# GPS_radiologger_v12.net
KiCad netlist of a schematic drawn in EAGLE
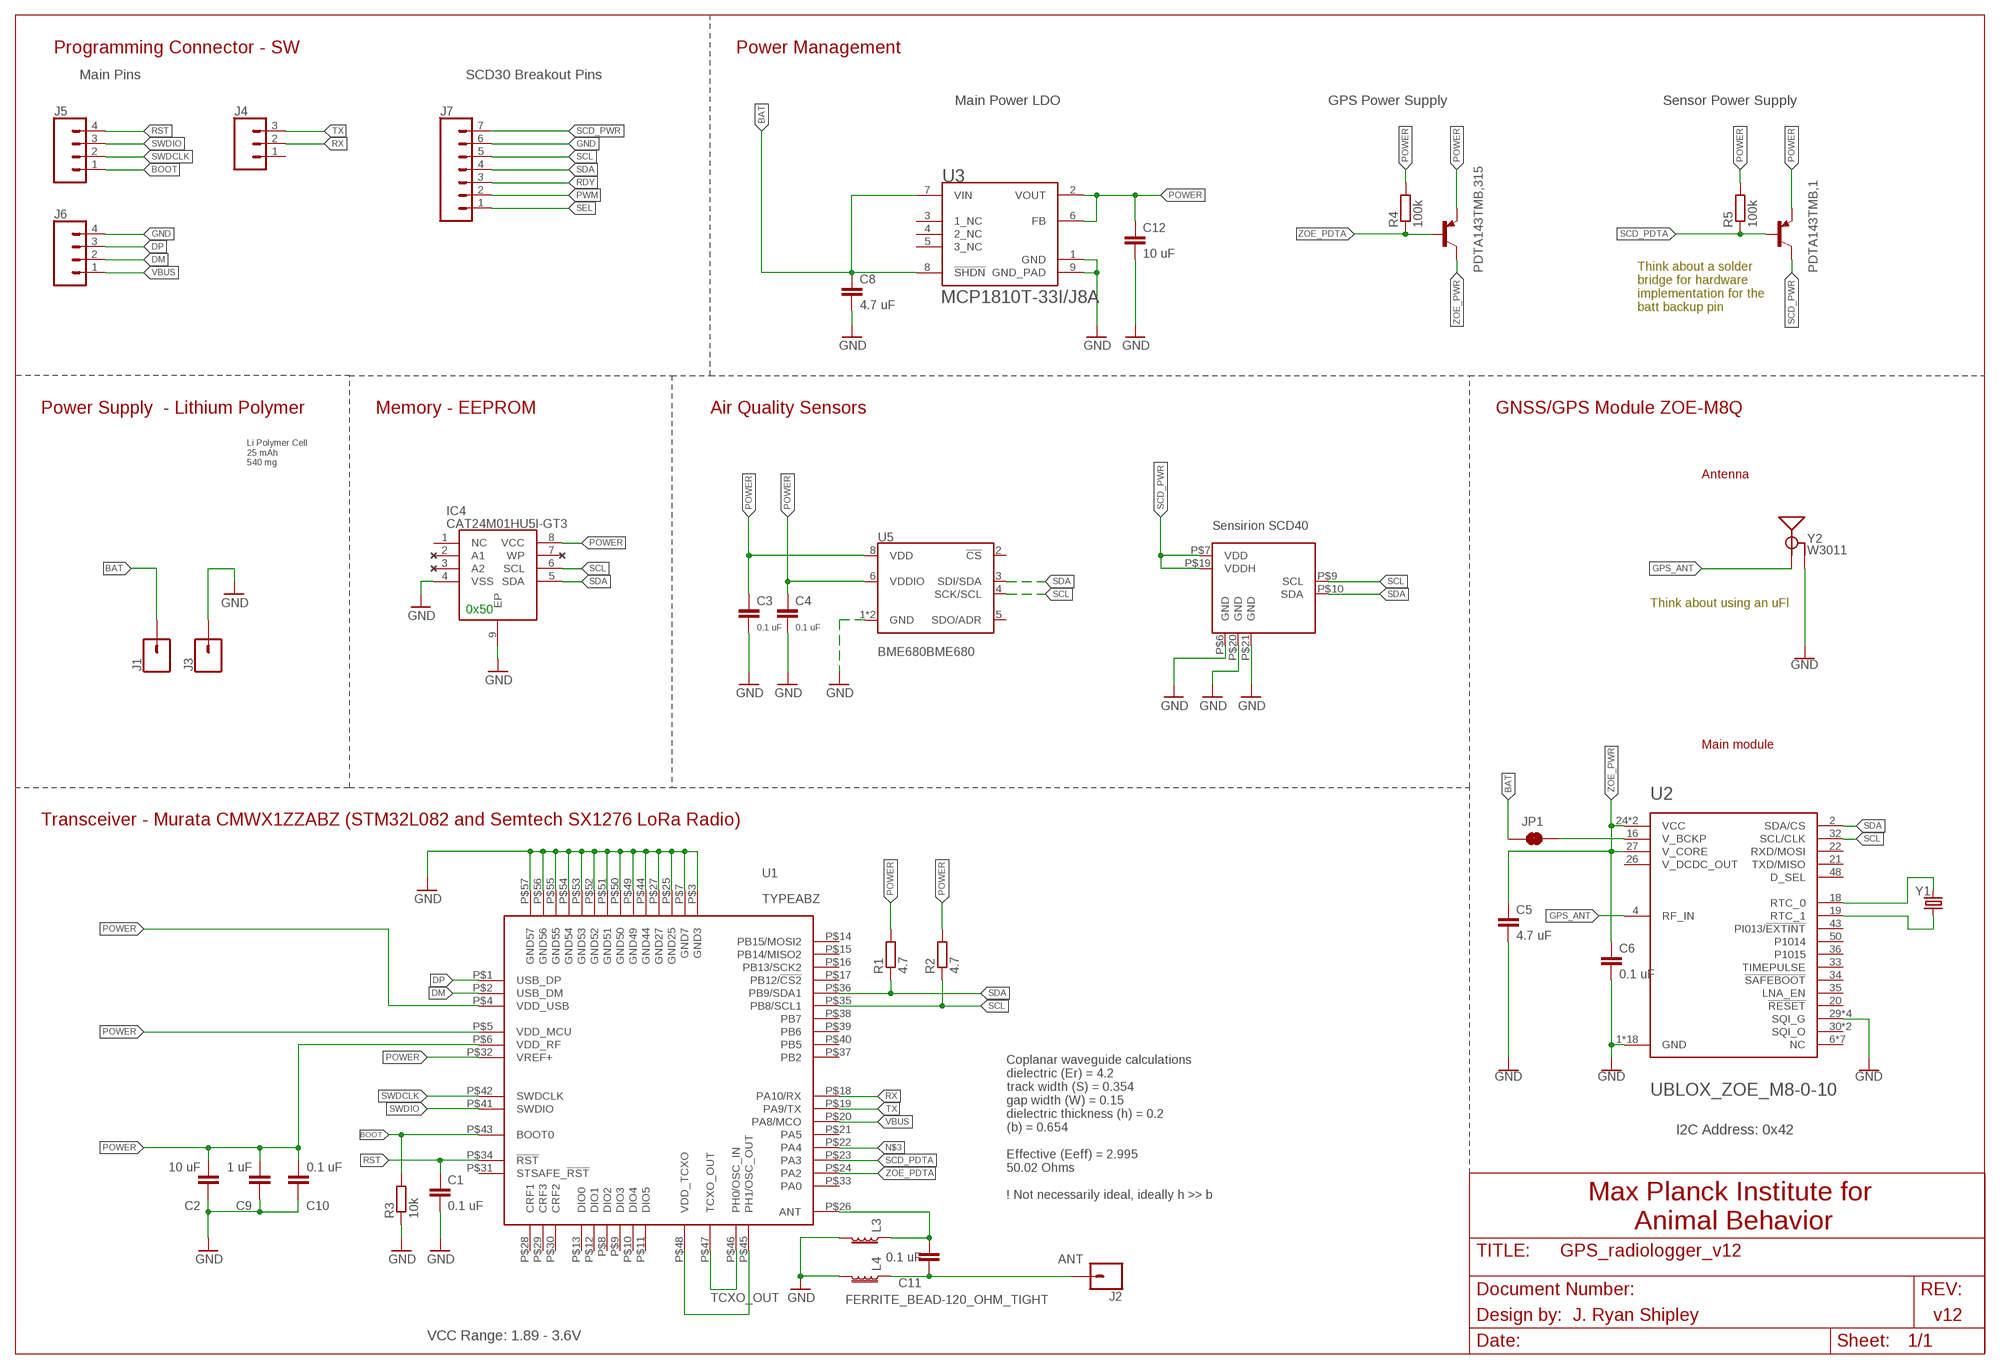
[diagram p0: schematic, sheet 1]

(export (version "E")
  (design (tool "Eeschema 10.0.6"))
  (components
    (comp (ref "C1")
      (value "0.1 uF")
      (footprint "eagle-import:C0201")
      (libsource (lib "eagle-import") (part "C-EUC0201"))
    )
    (comp (ref "C2")
      (value "10 uF")
      (footprint "eagle-import:C0201")
      (libsource (lib "eagle-import") (part "C-EUC0201"))
    )
    (comp (ref "C3")
      (value "0.1 uF")
      (footprint "eagle-import:C0201")
      (libsource (lib "eagle-import") (part "C-EUC0201"))
    )
    (comp (ref "C4")
      (value "0.1 uF")
      (footprint "eagle-import:C0201")
      (libsource (lib "eagle-import") (part "C-EUC0201"))
    )
    (comp (ref "C5")
      (value "4.7 uF")
      (footprint "eagle-import:C0201")
      (libsource (lib "eagle-import") (part "C-EUC0201"))
    )
    (comp (ref "C6")
      (value "0.1 uF")
      (footprint "eagle-import:C0201")
      (libsource (lib "eagle-import") (part "C-EUC0201"))
    )
    (comp (ref "C8")
      (value "4.7 uF")
      (footprint "eagle-import:C0201")
      (libsource (lib "eagle-import") (part "C-EUC0201"))
    )
    (comp (ref "C9")
      (value "1 uF")
      (footprint "eagle-import:C0201")
      (libsource (lib "eagle-import") (part "C-EUC0201"))
    )
    (comp (ref "C10")
      (value "0.1 uF")
      (footprint "eagle-import:C0201")
      (libsource (lib "eagle-import") (part "C-EUC0201"))
    )
    (comp (ref "C11")
      (value "0.1 uF")
      (footprint "eagle-import:C0201")
      (libsource (lib "eagle-import") (part "C-EUC0201"))
    )
    (comp (ref "C12")
      (value "10 uF")
      (footprint "eagle-import:C0201")
      (libsource (lib "eagle-import") (part "C-EUC0201"))
    )
    (comp (ref "IC4")
      (value "CAT24M01HU5I-GT3")
      (footprint "eagle-import:SON50P300X200X55-9N")
      (fields
        (field (name "MOUSER_PART_NUMBER") "863-CAT24M01HU5I-GT3")
        (field (name "RS_PART_NUMBER") "7814831P")
      )
      (libsource (lib "eagle-import") (part "CAT24M01HU5I-GT3"))
    )
    (comp (ref "J1")
      (value "CONN_01PTH_NO_SILK_YES_STOP")
      (footprint "eagle-import:1X01_NO_SILK")
      (libsource (lib "eagle-import") (part "CONN_01PTH_NO_SILK_YES_STOP"))
    )
    (comp (ref "J2")
      (value "CONN_01PTH_NO_SILK_SMALL")
      (footprint "eagle-import:1X01_SMALL")
      (libsource (lib "eagle-import") (part "CONN_01PTH_NO_SILK_SMALL"))
    )
    (comp (ref "J3")
      (value "CONN_01PTH_NO_SILK_YES_STOP")
      (footprint "eagle-import:1X01_NO_SILK")
      (libsource (lib "eagle-import") (part "CONN_01PTH_NO_SILK_YES_STOP"))
    )
    (comp (ref "J4")
      (value "CONN_031X03_1.27_NO_SILK")
      (footprint "eagle-import:1X03_1.27MM_NO_SILK")
      (libsource (lib "eagle-import") (part "CONN_031X03_1.27_NO_SILK"))
    )
    (comp (ref "J5")
      (value "CONN_041.27MM_NO_SILK")
      (footprint "eagle-import:1X04_1.27MM_NO_SILK")
      (libsource (lib "eagle-import") (part "CONN_041.27MM_NO_SILK"))
    )
    (comp (ref "J6")
      (value "CONN_041.27MM_NO_SILK")
      (footprint "eagle-import:1X04_1.27MM_NO_SILK")
      (libsource (lib "eagle-import") (part "CONN_041.27MM_NO_SILK"))
    )
    (comp (ref "J7")
      (value "CONN_07NO_SILK")
      (footprint "eagle-import:1X07_NO_SILK")
      (libsource (lib "eagle-import") (part "CONN_07NO_SILK"))
    )
    (comp (ref "JP1")
      (value "JUMPER-SMT_2_NC_TRACE_NO-SILK")
      (footprint "eagle-import:SMT-JUMPER_2_NC_TRACE_NO-SILK")
      (libsource (lib "eagle-import") (part "JUMPER-SMT_2_NC_TRACE_NO-SILK"))
    )
    (comp (ref "L3")
      (value "FERRITE_BEAD-120_OHM_TIGHT")
      (footprint "eagle-import:0402-TIGHT")
      (libsource (lib "eagle-import") (part "FERRITE_BEAD-120_OHM_TIGHT"))
    )
    (comp (ref "L4")
      (value "FERRITE_BEAD-120_OHM_TIGHT")
      (footprint "eagle-import:0402-TIGHT")
      (libsource (lib "eagle-import") (part "FERRITE_BEAD-120_OHM_TIGHT"))
    )
    (comp (ref "PDTA143TMB,1")
      (value "TINYPICO-PNPAMB")
      (footprint "eagle-import:SOT883(B)")
      (libsource (lib "eagle-import") (part "TINYPICO-PNPMBA"))
    )
    (comp (ref "PDTA143TMB,315")
      (value "TINYPICO-PNPAMB")
      (footprint "eagle-import:SOT883(B)")
      (libsource (lib "eagle-import") (part "TINYPICO-PNPMBA"))
    )
    (comp (ref "R1")
      (value "4.7")
      (footprint "eagle-import:R0201")
      (libsource (lib "eagle-import") (part "R-EU_R0201"))
    )
    (comp (ref "R2")
      (value "4.7")
      (footprint "eagle-import:R0201")
      (libsource (lib "eagle-import") (part "R-EU_R0201"))
    )
    (comp (ref "R3")
      (value "10k")
      (footprint "eagle-import:R0201")
      (libsource (lib "eagle-import") (part "R-EU_R0201"))
    )
    (comp (ref "R4")
      (value "100k")
      (footprint "eagle-import:R0201")
      (libsource (lib "eagle-import") (part "R-EU_R0201"))
    )
    (comp (ref "R5")
      (value "100k")
      (footprint "eagle-import:R0201")
      (libsource (lib "eagle-import") (part "R-EU_R0201"))
    )
    (comp (ref "U$1")
      (value "SCD40")
      (footprint "eagle-import:SCD40_LGA")
      (libsource (lib "eagle-import") (part "SCD40"))
    )
    (comp (ref "U1")
      (value "TYPEABZ")
      (footprint "eagle-import:TYPEABZ")
      (libsource (lib "eagle-import") (part "TYPEABZ"))
    )
    (comp (ref "U2")
      (value "UBLOX_ZOE_M8-0-10")
      (footprint "eagle-import:UBLOX_ZOE_M8-0-10")
      (libsource (lib "eagle-import") (part "UBLOX_ZOE_M8-0-10"))
    )
    (comp (ref "U3")
      (value "MICROCHIP_MCP1810T-33I-J8AMICROCHIP_MCP1810T-33I-J8A_0_0")
      (footprint "eagle-import:MICROCHIP_MCP1810T-33I-J8A_0")
      (fields
        (field (name "DIGIKEY_PART_NUMBER") "MCP1810T-33I/J8ACT-ND")
        (field (name "MF") "Microchip")
        (field (name "MOUSER_PART_NUMBER") "579-MCP1810T-33I/J8A")
      )
      (libsource (lib "eagle-import") (part "MICROCHIP_MCP1810T-33I-J8AMICROCHIP_MCP1810T-33I-J8A_0_0"))
    )
    (comp (ref "U5")
      (value "BME680BME680")
      (footprint "eagle-import:LGA3.0X3.0")
      (libsource (lib "eagle-import") (part "BME680BME680"))
    )
    (comp (ref "Y1")
      (value "32.768kHz")
      (footprint "eagle-import:CRYSTAL-SMD-1.0X1.2MM")
      (libsource (lib "eagle-import") (part "CRYSTAL-32.768KHZ"))
    )
    (comp (ref "Y2")
      (value "W3011")
      (footprint "eagle-import:W3011")
      (libsource (lib "eagle-import") (part "GPS_CHIP_ANTENNAW3011"))
    )
  )
  (nets
    (net (code "1") (name "/ANT") (class "Default")
      (node (ref "C11") (pin "1") (pinfunction "1_1") (pintype "passive"))
      (node (ref "J2") (pin "P$1") (pinfunction "1_P$1") (pintype "passive"))
      (node (ref "L4") (pin "1") (pinfunction "1_1") (pintype "passive"))
    )
    (net (code "2") (name "/TCXO_OUT") (class "Default")
      (node (ref "U1") (pin "P$46") (pinfunction "PH0/OSC_IN_P$46") (pintype "bidirectional"))
      (node (ref "U1") (pin "P$47") (pinfunction "TCXO_OUT_P$47") (pintype "bidirectional"))
    )
    (net (code "3") (name "/V_DCDC_OUT") (class "Default")
      (node (ref "U2") (pin "26") (pinfunction "V_DCDC_OUT_26") (pintype "power_in"))
    )
    (net (code "4") (name "BAT") (class "Default")
      (node (ref "C8") (pin "1") (pinfunction "1_1") (pintype "passive"))
      (node (ref "J1") (pin "1") (pinfunction "1_1") (pintype "passive"))
      (node (ref "JP1") (pin "1") (pinfunction "1_1") (pintype "passive"))
      (node (ref "U3") (pin "7") (pinfunction "VIN_7") (pintype "bidirectional"))
      (node (ref "U3") (pin "8") (pinfunction "~{SHDN}_8") (pintype "bidirectional"))
    )
    (net (code "5") (name "BOOT") (class "Default")
      (node (ref "J5") (pin "1") (pinfunction "1_1") (pintype "passive"))
      (node (ref "R3") (pin "2") (pinfunction "2_2") (pintype "passive"))
      (node (ref "U1") (pin "P$43") (pinfunction "BOOT0_P$43") (pintype "bidirectional"))
    )
    (net (code "6") (name "DM") (class "Default")
      (node (ref "J6") (pin "2") (pinfunction "2_2") (pintype "passive"))
      (node (ref "U1") (pin "P$2") (pinfunction "USB_DM_P$2") (pintype "bidirectional"))
    )
    (net (code "7") (name "DP") (class "Default")
      (node (ref "J6") (pin "3") (pinfunction "3_3") (pintype "passive"))
      (node (ref "U1") (pin "P$1") (pinfunction "USB_DP_P$1") (pintype "bidirectional"))
    )
    (net (code "8") (name "GND") (class "Default")
      (node (ref "C1") (pin "2") (pinfunction "2_2") (pintype "passive"))
      (node (ref "C10") (pin "1") (pinfunction "1_1") (pintype "passive"))
      (node (ref "C12") (pin "2") (pinfunction "2_2") (pintype "passive"))
      (node (ref "C2") (pin "1") (pinfunction "1_1") (pintype "passive"))
      (node (ref "C3") (pin "2") (pinfunction "2_2") (pintype "passive"))
      (node (ref "C4") (pin "2") (pinfunction "2_2") (pintype "passive"))
      (node (ref "C5") (pin "2") (pinfunction "2_2") (pintype "passive"))
      (node (ref "C6") (pin "2") (pinfunction "2_2") (pintype "passive"))
      (node (ref "C8") (pin "2") (pinfunction "2_2") (pintype "passive"))
      (node (ref "C9") (pin "1") (pinfunction "1_1") (pintype "passive"))
      (node (ref "IC4") (pin "4") (pinfunction "VSS_4") (pintype "power_in"))
      (node (ref "IC4") (pin "9") (pinfunction "EP_9") (pintype "bidirectional"))
      (node (ref "J3") (pin "1") (pinfunction "1_1") (pintype "passive"))
      (node (ref "J6") (pin "4") (pinfunction "4_4") (pintype "passive"))
      (node (ref "J7") (pin "6") (pinfunction "6_6") (pintype "passive"))
      (node (ref "L3") (pin "2") (pinfunction "2_2") (pintype "passive"))
      (node (ref "L4") (pin "2") (pinfunction "2_2") (pintype "passive"))
      (node (ref "R3") (pin "1") (pinfunction "1_1") (pintype "passive"))
      (node (ref "U$1") (pin "P$20") (pinfunction "GND_P$20") (pintype "bidirectional"))
      (node (ref "U$1") (pin "P$21") (pinfunction "GND_P$21") (pintype "bidirectional"))
      (node (ref "U$1") (pin "P$6") (pinfunction "GND_P$6") (pintype "bidirectional"))
      (node (ref "U1") (pin "P$25") (pinfunction "GND25_P$25") (pintype "power_in"))
      (node (ref "U1") (pin "P$27") (pinfunction "GND27_P$27") (pintype "power_in"))
      (node (ref "U1") (pin "P$3") (pinfunction "GND3_P$3") (pintype "power_in"))
      (node (ref "U1") (pin "P$44") (pinfunction "GND44_P$44") (pintype "power_in"))
      (node (ref "U1") (pin "P$49") (pinfunction "GND49_P$49") (pintype "power_in"))
      (node (ref "U1") (pin "P$50") (pinfunction "GND50_P$50") (pintype "power_in"))
      (node (ref "U1") (pin "P$51") (pinfunction "GND51_P$51") (pintype "power_in"))
      (node (ref "U1") (pin "P$52") (pinfunction "GND52_P$52") (pintype "power_in"))
      (node (ref "U1") (pin "P$53") (pinfunction "GND53_P$53") (pintype "power_in"))
      (node (ref "U1") (pin "P$54") (pinfunction "GND54_P$54") (pintype "power_in"))
      (node (ref "U1") (pin "P$55") (pinfunction "GND55_P$55") (pintype "power_in"))
      (node (ref "U1") (pin "P$56") (pinfunction "GND56_P$56") (pintype "power_in"))
      (node (ref "U1") (pin "P$57") (pinfunction "GND57_P$57") (pintype "power_in"))
      (node (ref "U1") (pin "P$7") (pinfunction "GND7_P$7") (pintype "power_in"))
      (node (ref "U2") (pin "1") (pinfunction "GND_1") (pintype "power_in"))
      (node (ref "U2") (pin "10") (pinfunction "GND_10") (pintype "power_in"))
      (node (ref "U2") (pin "11") (pinfunction "GND_11") (pintype "power_in"))
      (node (ref "U2") (pin "12") (pinfunction "GND_12") (pintype "power_in"))
      (node (ref "U2") (pin "17") (pinfunction "GND_17") (pintype "power_in"))
      (node (ref "U2") (pin "23") (pinfunction "GND_23") (pintype "power_in"))
      (node (ref "U2") (pin "29") (pinfunction "SQI_G_29") (pintype "bidirectional"))
      (node (ref "U2") (pin "3") (pinfunction "GND_3") (pintype "power_in"))
      (node (ref "U2") (pin "31") (pinfunction "SQI_G_31") (pintype "bidirectional"))
      (node (ref "U2") (pin "37") (pinfunction "GND_37") (pintype "power_in"))
      (node (ref "U2") (pin "38") (pinfunction "GND_38") (pintype "power_in"))
      (node (ref "U2") (pin "39") (pinfunction "GND_39") (pintype "power_in"))
      (node (ref "U2") (pin "40") (pinfunction "GND_40") (pintype "power_in"))
      (node (ref "U2") (pin "41") (pinfunction "GND_41") (pintype "power_in"))
      (node (ref "U2") (pin "44") (pinfunction "GND_44") (pintype "power_in"))
      (node (ref "U2") (pin "46") (pinfunction "SQI_G_46") (pintype "bidirectional"))
      (node (ref "U2") (pin "47") (pinfunction "SQI_G_47") (pintype "bidirectional"))
      (node (ref "U2") (pin "49") (pinfunction "GND_49") (pintype "power_in"))
      (node (ref "U2") (pin "5") (pinfunction "GND_5") (pintype "power_in"))
      (node (ref "U2") (pin "7") (pinfunction "GND_7") (pintype "power_in"))
      (node (ref "U2") (pin "8") (pinfunction "GND_8") (pintype "power_in"))
      (node (ref "U2") (pin "9") (pinfunction "GND_9") (pintype "power_in"))
      (node (ref "U3") (pin "1") (pinfunction "GND_1") (pintype "bidirectional"))
      (node (ref "U3") (pin "9") (pinfunction "GND_PAD_9") (pintype "bidirectional"))
      (node (ref "U5") (pin "1") (pinfunction "GND_1") (pintype "bidirectional"))
      (node (ref "U5") (pin "7") (pinfunction "GND_7") (pintype "bidirectional"))
      (node (ref "Y2") (pin "2") (pinfunction "GND_2") (pintype "bidirectional"))
      (node (ref "Y2") (pin "3") (pinfunction "GND_3") (pintype "bidirectional"))
    )
    (net (code "9") (name "GPS_ANT") (class "Default")
      (node (ref "U2") (pin "4") (pinfunction "RF_IN_4") (pintype "bidirectional"))
      (node (ref "Y2") (pin "1") (pinfunction "SIGNAL_1") (pintype "bidirectional"))
    )
    (net (code "10") (name "N$3") (class "Default")
      (node (ref "U1") (pin "P$22") (pinfunction "PA4_P$22") (pintype "bidirectional"))
    )
    (net (code "11") (name "Net-(U1-ANT)") (class "Default")
      (node (ref "C11") (pin "2") (pinfunction "2_2") (pintype "passive"))
      (node (ref "L3") (pin "1") (pinfunction "1_1") (pintype "passive"))
      (node (ref "U1") (pin "P$26") (pinfunction "ANT_P$26") (pintype "bidirectional"))
    )
    (net (code "12") (name "Net-(U1-PH1{slash}OSC_OUT)") (class "Default")
      (node (ref "U1") (pin "P$45") (pinfunction "PH1/OSC_OUT_P$45") (pintype "bidirectional"))
      (node (ref "U1") (pin "P$48") (pinfunction "VDD_TCXO_P$48") (pintype "power_in"))
    )
    (net (code "13") (name "Net-(U2-RTC_0)") (class "Default")
      (node (ref "U2") (pin "18") (pinfunction "RTC_0_18") (pintype "bidirectional"))
      (node (ref "Y1") (pin "P$2") (pinfunction "2_P$2") (pintype "passive"))
    )
    (net (code "14") (name "Net-(U2-RTC_1)") (class "Default")
      (node (ref "U2") (pin "19") (pinfunction "RTC_1_19") (pintype "bidirectional"))
      (node (ref "Y1") (pin "P$1") (pinfunction "1_P$1") (pintype "passive"))
    )
    (net (code "15") (name "Net-(U2-V_BCKP)") (class "Default")
      (node (ref "JP1") (pin "2") (pinfunction "2_2") (pintype "passive"))
      (node (ref "U2") (pin "16") (pinfunction "V_BCKP_16") (pintype "power_in"))
    )
    (net (code "16") (name "POWER") (class "Default")
      (node (ref "C10") (pin "2") (pinfunction "2_2") (pintype "passive"))
      (node (ref "C12") (pin "1") (pinfunction "1_1") (pintype "passive"))
      (node (ref "C2") (pin "2") (pinfunction "2_2") (pintype "passive"))
      (node (ref "C3") (pin "1") (pinfunction "1_1") (pintype "passive"))
      (node (ref "C4") (pin "1") (pinfunction "1_1") (pintype "passive"))
      (node (ref "C9") (pin "2") (pinfunction "2_2") (pintype "passive"))
      (node (ref "IC4") (pin "8") (pinfunction "VCC_8") (pintype "power_in"))
      (node (ref "PDTA143TMB,1") (pin "2") (pinfunction "E_2") (pintype "passive"))
      (node (ref "PDTA143TMB,315") (pin "2") (pinfunction "E_2") (pintype "passive"))
      (node (ref "R1") (pin "2") (pinfunction "2_2") (pintype "passive"))
      (node (ref "R2") (pin "2") (pinfunction "2_2") (pintype "passive"))
      (node (ref "R4") (pin "2") (pinfunction "2_2") (pintype "passive"))
      (node (ref "R5") (pin "2") (pinfunction "2_2") (pintype "passive"))
      (node (ref "U1") (pin "P$32") (pinfunction "VREF+_P$32") (pintype "power_in"))
      (node (ref "U1") (pin "P$4") (pinfunction "VDD_USB_P$4") (pintype "power_in"))
      (node (ref "U1") (pin "P$5") (pinfunction "VDD_MCU_P$5") (pintype "power_in"))
      (node (ref "U1") (pin "P$6") (pinfunction "VDD_RF_P$6") (pintype "power_in"))
      (node (ref "U3") (pin "2") (pinfunction "VOUT_2") (pintype "bidirectional"))
      (node (ref "U3") (pin "6") (pinfunction "FB_6") (pintype "bidirectional"))
      (node (ref "U5") (pin "6") (pinfunction "VDDIO_6") (pintype "bidirectional"))
      (node (ref "U5") (pin "8") (pinfunction "VDD_8") (pintype "bidirectional"))
    )
    (net (code "17") (name "PWM") (class "Default")
      (node (ref "J7") (pin "2") (pinfunction "2_2") (pintype "passive"))
    )
    (net (code "18") (name "RDY") (class "Default")
      (node (ref "J7") (pin "3") (pinfunction "3_3") (pintype "passive"))
    )
    (net (code "19") (name "RST") (class "Default")
      (node (ref "C1") (pin "1") (pinfunction "1_1") (pintype "passive"))
      (node (ref "J5") (pin "4") (pinfunction "4_4") (pintype "passive"))
      (node (ref "U1") (pin "P$34") (pinfunction "~{RST}_P$34") (pintype "bidirectional"))
    )
    (net (code "20") (name "RX") (class "Default")
      (node (ref "J4") (pin "2") (pinfunction "2_2") (pintype "passive"))
      (node (ref "U1") (pin "P$18") (pinfunction "PA10/RX_P$18") (pintype "bidirectional"))
    )
    (net (code "21") (name "SCD_PDTA") (class "Default")
      (node (ref "PDTA143TMB,1") (pin "1") (pinfunction "B_1") (pintype "passive"))
      (node (ref "R5") (pin "1") (pinfunction "1_1") (pintype "passive"))
      (node (ref "U1") (pin "P$23") (pinfunction "PA3_P$23") (pintype "bidirectional"))
    )
    (net (code "22") (name "SCD_PWR") (class "Default")
      (node (ref "J7") (pin "7") (pinfunction "7_7") (pintype "passive"))
      (node (ref "PDTA143TMB,1") (pin "3") (pinfunction "C_3") (pintype "passive"))
      (node (ref "U$1") (pin "P$19") (pinfunction "VDDH_P$19") (pintype "bidirectional"))
      (node (ref "U$1") (pin "P$7") (pinfunction "VDD_P$7") (pintype "bidirectional"))
    )
    (net (code "23") (name "SCL") (class "Default")
      (node (ref "IC4") (pin "6") (pinfunction "SCL_6") (pintype "bidirectional"))
      (node (ref "J7") (pin "5") (pinfunction "5_5") (pintype "passive"))
      (node (ref "R2") (pin "1") (pinfunction "1_1") (pintype "passive"))
      (node (ref "U$1") (pin "P$9") (pinfunction "SCL_P$9") (pintype "bidirectional"))
      (node (ref "U1") (pin "P$35") (pinfunction "PB8/SCL1_P$35") (pintype "bidirectional"))
      (node (ref "U2") (pin "32") (pinfunction "SCL/CLK_32") (pintype "bidirectional"))
      (node (ref "U5") (pin "4") (pinfunction "SCK/SCL_4") (pintype "bidirectional"))
    )
    (net (code "24") (name "SDA") (class "Default")
      (node (ref "IC4") (pin "5") (pinfunction "SDA_5") (pintype "bidirectional"))
      (node (ref "J7") (pin "4") (pinfunction "4_4") (pintype "passive"))
      (node (ref "R1") (pin "1") (pinfunction "1_1") (pintype "passive"))
      (node (ref "U$1") (pin "P$10") (pinfunction "SDA_P$10") (pintype "bidirectional"))
      (node (ref "U1") (pin "P$36") (pinfunction "PB9/SDA1_P$36") (pintype "bidirectional"))
      (node (ref "U2") (pin "2") (pinfunction "SDA/CS_2") (pintype "bidirectional"))
      (node (ref "U5") (pin "3") (pinfunction "SDI/SDA_3") (pintype "bidirectional"))
    )
    (net (code "25") (name "SEL") (class "Default")
      (node (ref "J7") (pin "1") (pinfunction "1_1") (pintype "passive"))
    )
    (net (code "26") (name "SWDCLK") (class "Default")
      (node (ref "J5") (pin "2") (pinfunction "2_2") (pintype "passive"))
      (node (ref "U1") (pin "P$42") (pinfunction "SWDCLK_P$42") (pintype "bidirectional"))
    )
    (net (code "27") (name "SWDIO") (class "Default")
      (node (ref "J5") (pin "3") (pinfunction "3_3") (pintype "passive"))
      (node (ref "U1") (pin "P$41") (pinfunction "SWDIO_P$41") (pintype "bidirectional"))
    )
    (net (code "28") (name "TX") (class "Default")
      (node (ref "J4") (pin "3") (pinfunction "3_3") (pintype "passive"))
      (node (ref "U1") (pin "P$19") (pinfunction "PA9/TX_P$19") (pintype "bidirectional"))
    )
    (net (code "29") (name "VBUS") (class "Default")
      (node (ref "J6") (pin "1") (pinfunction "1_1") (pintype "passive"))
      (node (ref "U1") (pin "P$20") (pinfunction "PA8/MCO_P$20") (pintype "bidirectional"))
    )
    (net (code "30") (name "ZOE_PDTA") (class "Default")
      (node (ref "PDTA143TMB,315") (pin "1") (pinfunction "B_1") (pintype "passive"))
      (node (ref "R4") (pin "1") (pinfunction "1_1") (pintype "passive"))
      (node (ref "U1") (pin "P$24") (pinfunction "PA2_P$24") (pintype "bidirectional"))
    )
    (net (code "31") (name "ZOE_PWR") (class "Default")
      (node (ref "C5") (pin "1") (pinfunction "1_1") (pintype "passive"))
      (node (ref "C6") (pin "1") (pinfunction "1_1") (pintype "passive"))
      (node (ref "PDTA143TMB,315") (pin "3") (pinfunction "C_3") (pintype "passive"))
      (node (ref "U2") (pin "24") (pinfunction "VCC_24") (pintype "power_in"))
      (node (ref "U2") (pin "25") (pinfunction "VCC_25") (pintype "power_in"))
      (node (ref "U2") (pin "27") (pinfunction "V_CORE_27") (pintype "power_in"))
    )
    (net (code "32") (name "unconnected-(IC4-A1-Pad2)") (class "Default")
      (node (ref "IC4") (pin "2") (pinfunction "A1_2") (pintype "bidirectional"))
    )
    (net (code "33") (name "unconnected-(IC4-A2-Pad3)") (class "Default")
      (node (ref "IC4") (pin "3") (pinfunction "A2_3") (pintype "bidirectional"))
    )
    (net (code "34") (name "unconnected-(IC4-NC-Pad1)") (class "Default")
      (node (ref "IC4") (pin "1") (pinfunction "NC_1") (pintype "no_connect"))
    )
    (net (code "35") (name "unconnected-(IC4-WP-Pad7)") (class "Default")
      (node (ref "IC4") (pin "7") (pinfunction "WP_7") (pintype "bidirectional"))
    )
    (net (code "36") (name "unconnected-(J4-Pad1)") (class "Default")
      (node (ref "J4") (pin "1") (pinfunction "1_1") (pintype "passive"))
    )
    (net (code "37") (name "unconnected-(U1-CRF1-PadP$28)") (class "Default")
      (node (ref "U1") (pin "P$28") (pinfunction "CRF1_P$28") (pintype "no_connect"))
    )
    (net (code "38") (name "unconnected-(U1-CRF2-PadP$30)") (class "Default")
      (node (ref "U1") (pin "P$30") (pinfunction "CRF2_P$30") (pintype "no_connect"))
    )
    (net (code "39") (name "unconnected-(U1-CRF3-PadP$29)") (class "Default")
      (node (ref "U1") (pin "P$29") (pinfunction "CRF3_P$29") (pintype "no_connect"))
    )
    (net (code "40") (name "unconnected-(U1-DIO0-PadP$13)") (class "Default")
      (node (ref "U1") (pin "P$13") (pinfunction "DIO0_P$13") (pintype "no_connect"))
    )
    (net (code "41") (name "unconnected-(U1-DIO1-PadP$12)") (class "Default")
      (node (ref "U1") (pin "P$12") (pinfunction "DIO1_P$12") (pintype "no_connect"))
    )
    (net (code "42") (name "unconnected-(U1-DIO2-PadP$8)") (class "Default")
      (node (ref "U1") (pin "P$8") (pinfunction "DIO2_P$8") (pintype "no_connect"))
    )
    (net (code "43") (name "unconnected-(U1-DIO3-PadP$9)") (class "Default")
      (node (ref "U1") (pin "P$9") (pinfunction "DIO3_P$9") (pintype "no_connect"))
    )
    (net (code "44") (name "unconnected-(U1-DIO4-PadP$10)") (class "Default")
      (node (ref "U1") (pin "P$10") (pinfunction "DIO4_P$10") (pintype "bidirectional"))
    )
    (net (code "45") (name "unconnected-(U1-DIO5-PadP$11)") (class "Default")
      (node (ref "U1") (pin "P$11") (pinfunction "DIO5_P$11") (pintype "bidirectional"))
    )
    (net (code "46") (name "unconnected-(U1-PA0-PadP$33)") (class "Default")
      (node (ref "U1") (pin "P$33") (pinfunction "PA0_P$33") (pintype "bidirectional"))
    )
    (net (code "47") (name "unconnected-(U1-PA5-PadP$21)") (class "Default")
      (node (ref "U1") (pin "P$21") (pinfunction "PA5_P$21") (pintype "bidirectional"))
    )
    (net (code "48") (name "unconnected-(U1-PB2-PadP$37)") (class "Default")
      (node (ref "U1") (pin "P$37") (pinfunction "PB2_P$37") (pintype "bidirectional"))
    )
    (net (code "49") (name "unconnected-(U1-PB5-PadP$40)") (class "Default")
      (node (ref "U1") (pin "P$40") (pinfunction "PB5_P$40") (pintype "bidirectional"))
    )
    (net (code "50") (name "unconnected-(U1-PB6-PadP$39)") (class "Default")
      (node (ref "U1") (pin "P$39") (pinfunction "PB6_P$39") (pintype "bidirectional"))
    )
    (net (code "51") (name "unconnected-(U1-PB7-PadP$38)") (class "Default")
      (node (ref "U1") (pin "P$38") (pinfunction "PB7_P$38") (pintype "bidirectional"))
    )
    (net (code "52") (name "unconnected-(U1-PB12{slash}~{CS2}-PadP$17)") (class "Default")
      (node (ref "U1") (pin "P$17") (pinfunction "PB12/~{CS2}_P$17") (pintype "bidirectional"))
    )
    (net (code "53") (name "unconnected-(U1-PB13{slash}SCK2-PadP$16)") (class "Default")
      (node (ref "U1") (pin "P$16") (pinfunction "PB13/SCK2_P$16") (pintype "bidirectional"))
    )
    (net (code "54") (name "unconnected-(U1-PB14{slash}MISO2-PadP$15)") (class "Default")
      (node (ref "U1") (pin "P$15") (pinfunction "PB14/MISO2_P$15") (pintype "bidirectional"))
    )
    (net (code "55") (name "unconnected-(U1-PB15{slash}MOSI2-PadP$14)") (class "Default")
      (node (ref "U1") (pin "P$14") (pinfunction "PB15/MOSI2_P$14") (pintype "bidirectional"))
    )
    (net (code "56") (name "unconnected-(U1-STSAFE_~{RST}-PadP$31)") (class "Default")
      (node (ref "U1") (pin "P$31") (pinfunction "STSAFE_~{RST}_P$31") (pintype "bidirectional"))
    )
    (net (code "57") (name "unconnected-(U2-D_SEL-Pad48)") (class "Default")
      (node (ref "U2") (pin "48") (pinfunction "D_SEL_48") (pintype "bidirectional"))
    )
    (net (code "58") (name "unconnected-(U2-LNA_EN-Pad35)") (class "Default")
      (node (ref "U2") (pin "35") (pinfunction "LNA_EN_35") (pintype "bidirectional"))
    )
    (net (code "59") (name "unconnected-(U2-NC-Pad6)") (class "Default")
      (node (ref "U2") (pin "6") (pinfunction "NC_6") (pintype "no_connect"))
    )
    (net (code "60") (name "unconnected-(U2-NC-Pad13)") (class "Default")
      (node (ref "U2") (pin "13") (pinfunction "NC_13") (pintype "no_connect"))
    )
    (net (code "61") (name "unconnected-(U2-NC-Pad14)") (class "Default")
      (node (ref "U2") (pin "14") (pinfunction "NC_14") (pintype "no_connect"))
    )
    (net (code "62") (name "unconnected-(U2-NC-Pad15)") (class "Default")
      (node (ref "U2") (pin "15") (pinfunction "NC_15") (pintype "no_connect"))
    )
    (net (code "63") (name "unconnected-(U2-NC-Pad28)") (class "Default")
      (node (ref "U2") (pin "28") (pinfunction "NC_28") (pintype "no_connect"))
    )
    (net (code "64") (name "unconnected-(U2-NC-Pad42)") (class "Default")
      (node (ref "U2") (pin "42") (pinfunction "NC_42") (pintype "no_connect"))
    )
    (net (code "65") (name "unconnected-(U2-NC-Pad51)") (class "Default")
      (node (ref "U2") (pin "51") (pinfunction "NC_51") (pintype "no_connect"))
    )
    (net (code "66") (name "unconnected-(U2-P1014-Pad50)") (class "Default")
      (node (ref "U2") (pin "50") (pinfunction "P1014_50") (pintype "bidirectional"))
    )
    (net (code "67") (name "unconnected-(U2-P1015-Pad36)") (class "Default")
      (node (ref "U2") (pin "36") (pinfunction "P1015_36") (pintype "bidirectional"))
    )
    (net (code "68") (name "unconnected-(U2-PI013{slash}~{EXTINT}-Pad43)") (class "Default")
      (node (ref "U2") (pin "43") (pinfunction "PI013/~{EXTINT}_43") (pintype "bidirectional"))
    )
    (net (code "69") (name "unconnected-(U2-RXD{slash}MOSI-Pad22)") (class "Default")
      (node (ref "U2") (pin "22") (pinfunction "RXD/MOSI_22") (pintype "bidirectional"))
    )
    (net (code "70") (name "unconnected-(U2-SQI_O-Pad30)") (class "Default")
      (node (ref "U2") (pin "30") (pinfunction "SQI_O_30") (pintype "no_connect"))
    )
    (net (code "71") (name "unconnected-(U2-SQI_O-Pad45)") (class "Default")
      (node (ref "U2") (pin "45") (pinfunction "SQI_O_45") (pintype "no_connect"))
    )
    (net (code "72") (name "unconnected-(U2-TIMEPULSE-Pad33)") (class "Default")
      (node (ref "U2") (pin "33") (pinfunction "TIMEPULSE_33") (pintype "bidirectional"))
    )
    (net (code "73") (name "unconnected-(U2-TXD{slash}MISO-Pad21)") (class "Default")
      (node (ref "U2") (pin "21") (pinfunction "TXD/MISO_21") (pintype "bidirectional"))
    )
    (net (code "74") (name "unconnected-(U2-~{RESET}-Pad20)") (class "Default")
      (node (ref "U2") (pin "20") (pinfunction "~{RESET}_20") (pintype "bidirectional"))
    )
    (net (code "75") (name "unconnected-(U2-~{SAFEBOOT}-Pad34)") (class "Default")
      (node (ref "U2") (pin "34") (pinfunction "~{SAFEBOOT}_34") (pintype "bidirectional"))
    )
    (net (code "76") (name "unconnected-(U3-1_NC-Pad3)") (class "Default")
      (node (ref "U3") (pin "3") (pinfunction "1_NC_3") (pintype "bidirectional"))
    )
    (net (code "77") (name "unconnected-(U3-2_NC-Pad4)") (class "Default")
      (node (ref "U3") (pin "4") (pinfunction "2_NC_4") (pintype "bidirectional"))
    )
    (net (code "78") (name "unconnected-(U3-3_NC-Pad5)") (class "Default")
      (node (ref "U3") (pin "5") (pinfunction "3_NC_5") (pintype "bidirectional"))
    )
    (net (code "79") (name "unconnected-(U5-SDO{slash}ADR-Pad5)") (class "Default")
      (node (ref "U5") (pin "5") (pinfunction "SDO/ADR_5") (pintype "bidirectional"))
    )
    (net (code "80") (name "unconnected-(U5-~{CS}-Pad2)") (class "Default")
      (node (ref "U5") (pin "2") (pinfunction "~{CS}_2") (pintype "bidirectional"))
    )
  )
)
